# LRF_Breakout.net
KiCad netlist of a schematic drawn in EAGLE
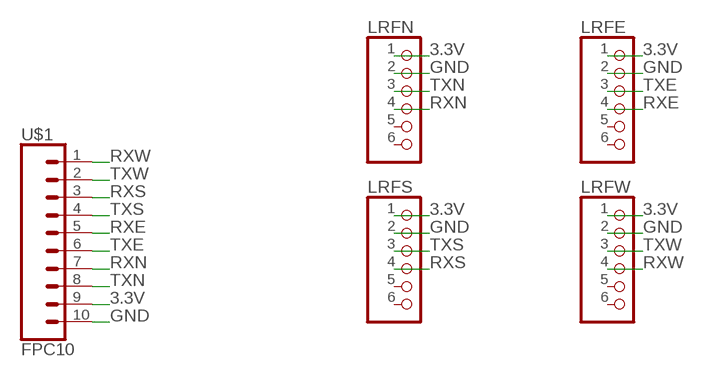
[diagram p0: schematic, sheet 1]

(export (version "E")
  (design (tool "Eeschema 10.0.6"))
  (components
    (comp (ref "LRFE")
      (value "PINHD-1X6")
      (footprint "eagle-import:1X06")
      (libsource (lib "eagle-import") (part "PINHD-1X6"))
    )
    (comp (ref "LRFN")
      (value "PINHD-1X6")
      (footprint "eagle-import:1X06")
      (libsource (lib "eagle-import") (part "PINHD-1X6"))
    )
    (comp (ref "LRFS")
      (value "PINHD-1X6")
      (footprint "eagle-import:1X06")
      (libsource (lib "eagle-import") (part "PINHD-1X6"))
    )
    (comp (ref "LRFW")
      (value "PINHD-1X6")
      (footprint "eagle-import:1X06")
      (libsource (lib "eagle-import") (part "PINHD-1X6"))
    )
    (comp (ref "U$1")
      (value "FPC10")
      (footprint "eagle-import:FPC10")
      (libsource (lib "eagle-import") (part "FPC10"))
    )
  )
  (nets
    (net (code "1") (name "/3.3V") (class "Default")
      (node (ref "LRFE") (pin "1") (pinfunction "1_1") (pintype "passive"))
      (node (ref "LRFN") (pin "1") (pinfunction "1_1") (pintype "passive"))
      (node (ref "LRFS") (pin "1") (pinfunction "1_1") (pintype "passive"))
      (node (ref "LRFW") (pin "1") (pinfunction "1_1") (pintype "passive"))
      (node (ref "U$1") (pin "9") (pinfunction "9_9") (pintype "passive"))
    )
    (net (code "2") (name "/GND") (class "Default")
      (node (ref "LRFE") (pin "2") (pinfunction "2_2") (pintype "passive"))
      (node (ref "LRFN") (pin "2") (pinfunction "2_2") (pintype "passive"))
      (node (ref "LRFS") (pin "2") (pinfunction "2_2") (pintype "passive"))
      (node (ref "LRFW") (pin "2") (pinfunction "2_2") (pintype "passive"))
      (node (ref "U$1") (pin "10") (pinfunction "10_10") (pintype "passive"))
    )
    (net (code "3") (name "/RXE") (class "Default")
      (node (ref "LRFE") (pin "4") (pinfunction "4_4") (pintype "passive"))
      (node (ref "U$1") (pin "5") (pinfunction "5_5") (pintype "passive"))
    )
    (net (code "4") (name "/RXN") (class "Default")
      (node (ref "LRFN") (pin "4") (pinfunction "4_4") (pintype "passive"))
      (node (ref "U$1") (pin "7") (pinfunction "7_7") (pintype "passive"))
    )
    (net (code "5") (name "/RXS") (class "Default")
      (node (ref "LRFS") (pin "4") (pinfunction "4_4") (pintype "passive"))
      (node (ref "U$1") (pin "3") (pinfunction "3_3") (pintype "passive"))
    )
    (net (code "6") (name "/RXW") (class "Default")
      (node (ref "LRFW") (pin "4") (pinfunction "4_4") (pintype "passive"))
      (node (ref "U$1") (pin "1") (pinfunction "1_1") (pintype "passive"))
    )
    (net (code "7") (name "/TXE") (class "Default")
      (node (ref "LRFE") (pin "3") (pinfunction "3_3") (pintype "passive"))
      (node (ref "U$1") (pin "6") (pinfunction "6_6") (pintype "passive"))
    )
    (net (code "8") (name "/TXN") (class "Default")
      (node (ref "LRFN") (pin "3") (pinfunction "3_3") (pintype "passive"))
      (node (ref "U$1") (pin "8") (pinfunction "8_8") (pintype "passive"))
    )
    (net (code "9") (name "/TXS") (class "Default")
      (node (ref "LRFS") (pin "3") (pinfunction "3_3") (pintype "passive"))
      (node (ref "U$1") (pin "4") (pinfunction "4_4") (pintype "passive"))
    )
    (net (code "10") (name "/TXW") (class "Default")
      (node (ref "LRFW") (pin "3") (pinfunction "3_3") (pintype "passive"))
      (node (ref "U$1") (pin "2") (pinfunction "2_2") (pintype "passive"))
    )
    (net (code "11") (name "unconnected-(LRFE-Pad5)") (class "Default")
      (node (ref "LRFE") (pin "5") (pinfunction "5_5") (pintype "passive"))
    )
    (net (code "12") (name "unconnected-(LRFE-Pad6)") (class "Default")
      (node (ref "LRFE") (pin "6") (pinfunction "6_6") (pintype "passive"))
    )
    (net (code "13") (name "unconnected-(LRFN-Pad5)") (class "Default")
      (node (ref "LRFN") (pin "5") (pinfunction "5_5") (pintype "passive"))
    )
    (net (code "14") (name "unconnected-(LRFN-Pad6)") (class "Default")
      (node (ref "LRFN") (pin "6") (pinfunction "6_6") (pintype "passive"))
    )
    (net (code "15") (name "unconnected-(LRFS-Pad5)") (class "Default")
      (node (ref "LRFS") (pin "5") (pinfunction "5_5") (pintype "passive"))
    )
    (net (code "16") (name "unconnected-(LRFS-Pad6)") (class "Default")
      (node (ref "LRFS") (pin "6") (pinfunction "6_6") (pintype "passive"))
    )
    (net (code "17") (name "unconnected-(LRFW-Pad5)") (class "Default")
      (node (ref "LRFW") (pin "5") (pinfunction "5_5") (pintype "passive"))
    )
    (net (code "18") (name "unconnected-(LRFW-Pad6)") (class "Default")
      (node (ref "LRFW") (pin "6") (pinfunction "6_6") (pintype "passive"))
    )
  )
)
